# 03_-_SAMA7G54-MPU.net
KiCad netlist of a schematic drawn in Altium Designer
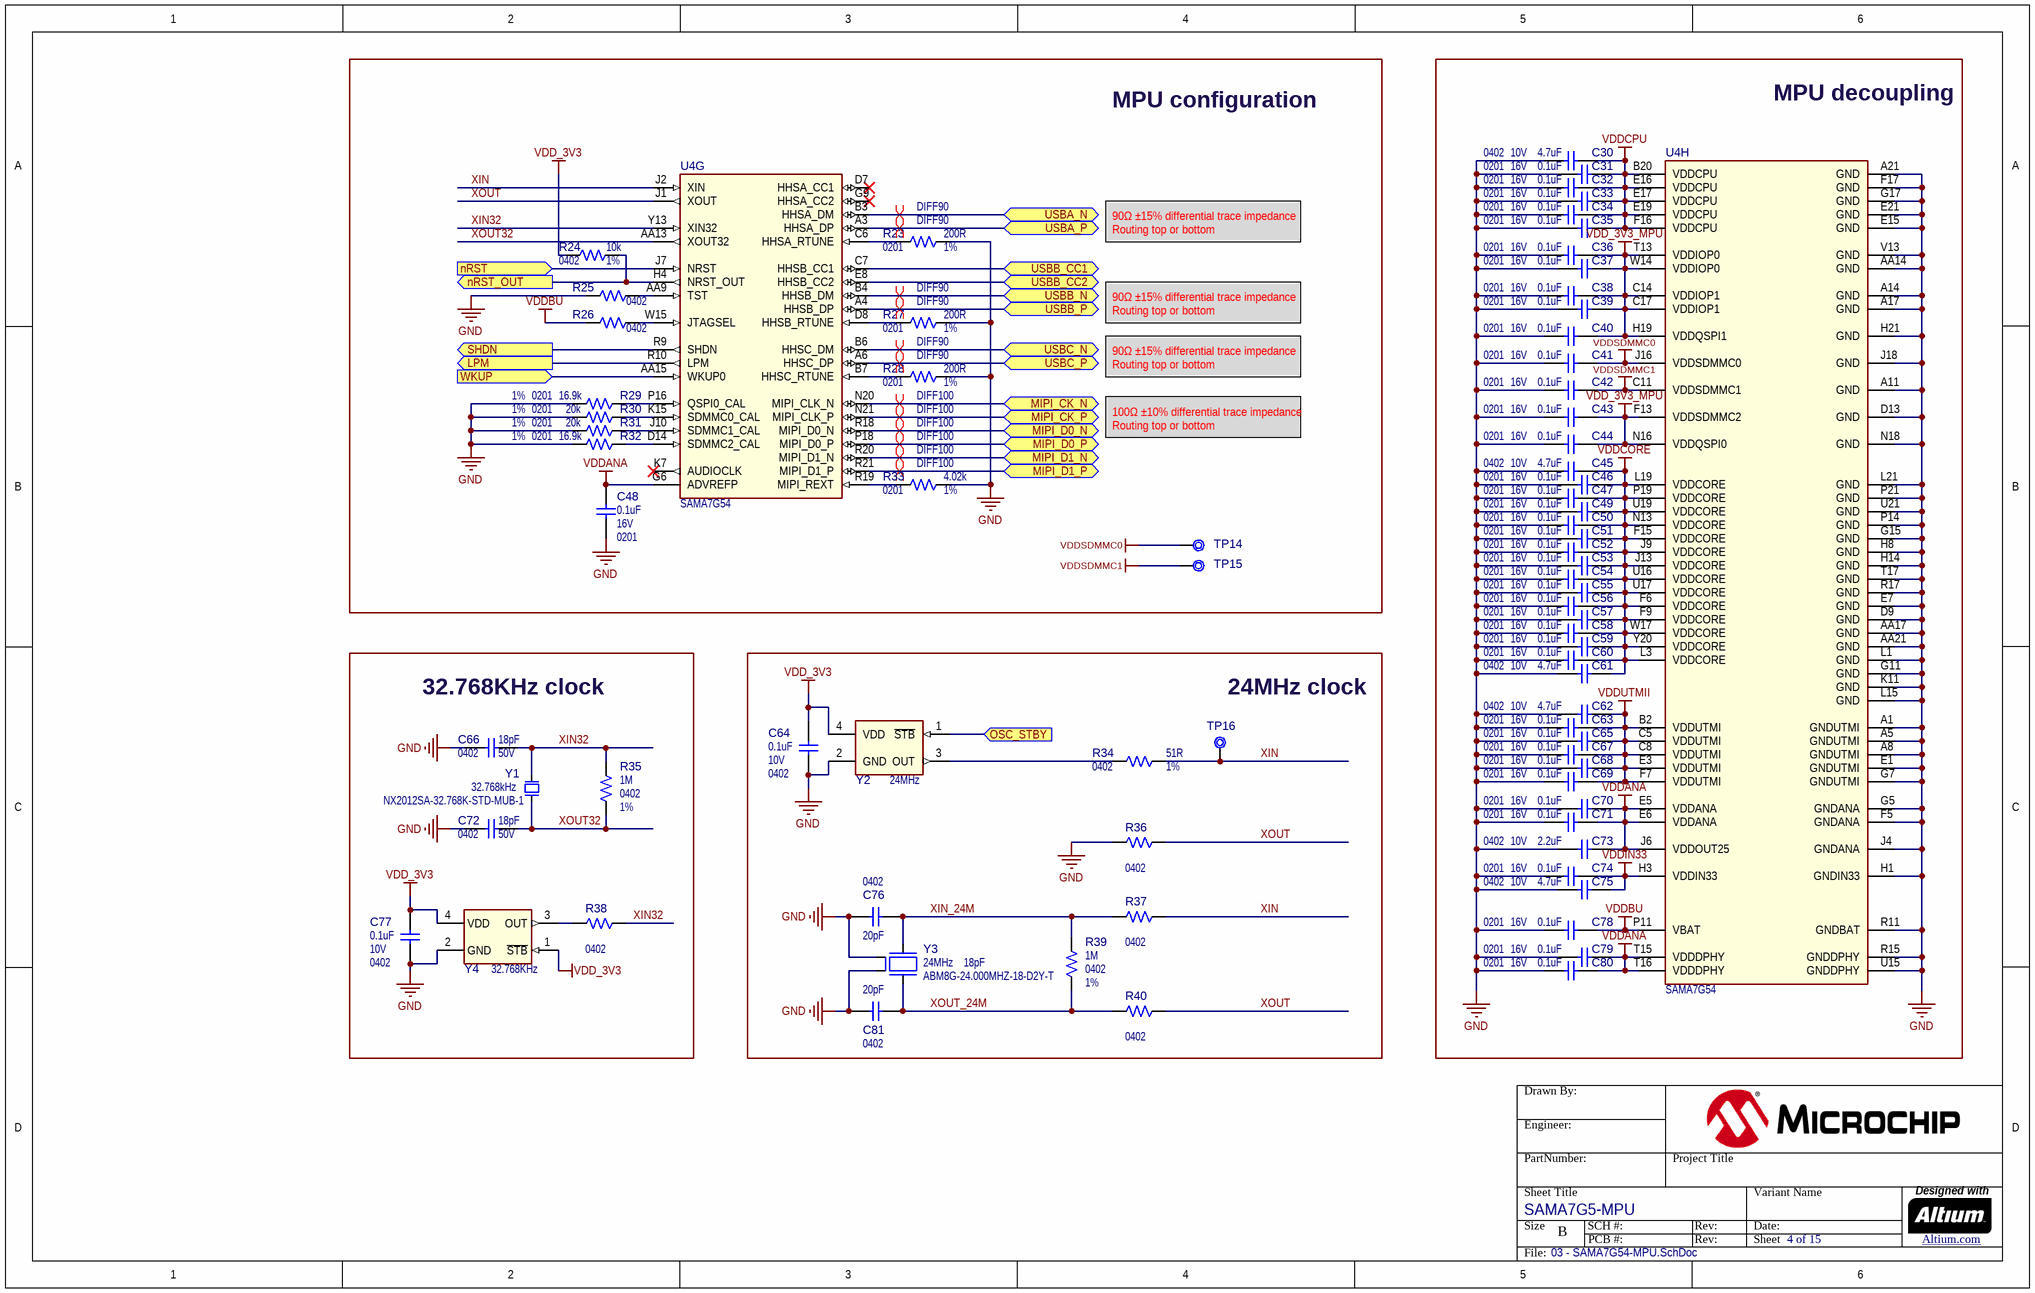
[diagram p0: 03 - SAMA7G54-MPU.SchDoc]

(export (version "E")
  (design (tool "Eeschema 10.0.6"))
  (components
    (comp (ref "C30")
      (value "4.7uF")
      (footprint "CAP_C_0402")
      (description "Capacitor")
      (fields
        (field (name "VOLTAGE") "10V")
        (field (name "PACKAGE") "0402")
        (field (name "TOLERANCE") "10%")
        (field (name "Comment") "Capacitor NP")
        (field (name "OWNER") "Jesus Aviles")
      )
      (libsource (lib "MCHP-CDB") (part "Capacitor NP"))
    )
    (comp (ref "C31")
      (value "0.1uF")
      (footprint "CAP_C_0201")
      (description "Capacitor")
      (fields
        (field (name "VOLTAGE") "16V")
        (field (name "PACKAGE") "0201")
        (field (name "TOLERANCE") "10%")
        (field (name "Comment") "Capacitor NP")
        (field (name "OWNER") "Dragos Danaila")
      )
      (libsource (lib "MCHP-CDB") (part "Capacitor NP"))
    )
    (comp (ref "C32")
      (value "0.1uF")
      (footprint "CAP_C_0201")
      (description "Capacitor")
      (fields
        (field (name "VOLTAGE") "16V")
        (field (name "PACKAGE") "0201")
        (field (name "TOLERANCE") "10%")
        (field (name "Comment") "Capacitor NP")
        (field (name "OWNER") "Dragos Danaila")
      )
      (libsource (lib "MCHP-CDB") (part "Capacitor NP"))
    )
    (comp (ref "C33")
      (value "0.1uF")
      (footprint "CAP_C_0201")
      (description "Capacitor")
      (fields
        (field (name "VOLTAGE") "16V")
        (field (name "PACKAGE") "0201")
        (field (name "TOLERANCE") "10%")
        (field (name "Comment") "Capacitor NP")
        (field (name "OWNER") "Dragos Danaila")
      )
      (libsource (lib "MCHP-CDB") (part "Capacitor NP"))
    )
    (comp (ref "C34")
      (value "0.1uF")
      (footprint "CAP_C_0201")
      (description "Capacitor")
      (fields
        (field (name "VOLTAGE") "16V")
        (field (name "PACKAGE") "0201")
        (field (name "TOLERANCE") "10%")
        (field (name "Comment") "Capacitor NP")
        (field (name "OWNER") "Dragos Danaila")
      )
      (libsource (lib "MCHP-CDB") (part "Capacitor NP"))
    )
    (comp (ref "C35")
      (value "0.1uF")
      (footprint "CAP_C_0201")
      (description "Capacitor")
      (fields
        (field (name "VOLTAGE") "16V")
        (field (name "PACKAGE") "0201")
        (field (name "TOLERANCE") "10%")
        (field (name "Comment") "Capacitor NP")
        (field (name "OWNER") "Dragos Danaila")
      )
      (libsource (lib "MCHP-CDB") (part "Capacitor NP"))
    )
    (comp (ref "C36")
      (value "0.1uF")
      (footprint "CAP_C_0201")
      (description "Capacitor")
      (fields
        (field (name "VOLTAGE") "16V")
        (field (name "PACKAGE") "0201")
        (field (name "TOLERANCE") "10%")
        (field (name "Comment") "Capacitor NP")
        (field (name "OWNER") "Dragos Danaila")
      )
      (libsource (lib "MCHP-CDB") (part "Capacitor NP"))
    )
    (comp (ref "C37")
      (value "0.1uF")
      (footprint "CAP_C_0201")
      (description "Capacitor")
      (fields
        (field (name "VOLTAGE") "16V")
        (field (name "PACKAGE") "0201")
        (field (name "TOLERANCE") "10%")
        (field (name "Comment") "Capacitor NP")
        (field (name "OWNER") "Dragos Danaila")
      )
      (libsource (lib "MCHP-CDB") (part "Capacitor NP"))
    )
    (comp (ref "C38")
      (value "0.1uF")
      (footprint "CAP_C_0201")
      (description "Capacitor")
      (fields
        (field (name "VOLTAGE") "16V")
        (field (name "PACKAGE") "0201")
        (field (name "TOLERANCE") "10%")
        (field (name "Comment") "Capacitor NP")
        (field (name "OWNER") "Dragos Danaila")
      )
      (libsource (lib "MCHP-CDB") (part "Capacitor NP"))
    )
    (comp (ref "C39")
      (value "0.1uF")
      (footprint "CAP_C_0201")
      (description "Capacitor")
      (fields
        (field (name "VOLTAGE") "16V")
        (field (name "PACKAGE") "0201")
        (field (name "TOLERANCE") "10%")
        (field (name "Comment") "Capacitor NP")
        (field (name "OWNER") "Dragos Danaila")
      )
      (libsource (lib "MCHP-CDB") (part "Capacitor NP"))
    )
    (comp (ref "C40")
      (value "0.1uF")
      (footprint "CAP_C_0201")
      (description "Capacitor")
      (fields
        (field (name "VOLTAGE") "16V")
        (field (name "PACKAGE") "0201")
        (field (name "TOLERANCE") "10%")
        (field (name "Comment") "Capacitor NP")
        (field (name "OWNER") "Dragos Danaila")
      )
      (libsource (lib "MCHP-CDB") (part "Capacitor NP"))
    )
    (comp (ref "C41")
      (value "0.1uF")
      (footprint "CAP_C_0201")
      (description "Capacitor")
      (fields
        (field (name "VOLTAGE") "16V")
        (field (name "PACKAGE") "0201")
        (field (name "TOLERANCE") "10%")
        (field (name "Comment") "Capacitor NP")
        (field (name "OWNER") "Dragos Danaila")
      )
      (libsource (lib "MCHP-CDB") (part "Capacitor NP"))
    )
    (comp (ref "C42")
      (value "0.1uF")
      (footprint "CAP_C_0201")
      (description "Capacitor")
      (fields
        (field (name "VOLTAGE") "16V")
        (field (name "PACKAGE") "0201")
        (field (name "TOLERANCE") "10%")
        (field (name "Comment") "Capacitor NP")
        (field (name "OWNER") "Dragos Danaila")
      )
      (libsource (lib "MCHP-CDB") (part "Capacitor NP"))
    )
    (comp (ref "C43")
      (value "0.1uF")
      (footprint "CAP_C_0201")
      (description "Capacitor")
      (fields
        (field (name "VOLTAGE") "16V")
        (field (name "PACKAGE") "0201")
        (field (name "TOLERANCE") "10%")
        (field (name "Comment") "Capacitor NP")
        (field (name "OWNER") "Dragos Danaila")
      )
      (libsource (lib "MCHP-CDB") (part "Capacitor NP"))
    )
    (comp (ref "C44")
      (value "0.1uF")
      (footprint "CAP_C_0201")
      (description "Capacitor")
      (fields
        (field (name "VOLTAGE") "16V")
        (field (name "PACKAGE") "0201")
        (field (name "TOLERANCE") "10%")
        (field (name "Comment") "Capacitor NP")
        (field (name "OWNER") "Dragos Danaila")
      )
      (libsource (lib "MCHP-CDB") (part "Capacitor NP"))
    )
    (comp (ref "C45")
      (value "4.7uF")
      (footprint "CAP_C_0402")
      (description "Capacitor")
      (fields
        (field (name "VOLTAGE") "10V")
        (field (name "PACKAGE") "0402")
        (field (name "TOLERANCE") "10%")
        (field (name "Comment") "Capacitor NP")
        (field (name "OWNER") "Jesus Aviles")
      )
      (libsource (lib "MCHP-CDB") (part "Capacitor NP"))
    )
    (comp (ref "C46")
      (value "0.1uF")
      (footprint "CAP_C_0201")
      (description "Capacitor")
      (fields
        (field (name "VOLTAGE") "16V")
        (field (name "PACKAGE") "0201")
        (field (name "TOLERANCE") "10%")
        (field (name "Comment") "Capacitor NP")
        (field (name "OWNER") "Dragos Danaila")
      )
      (libsource (lib "MCHP-CDB") (part "Capacitor NP"))
    )
    (comp (ref "C47")
      (value "0.1uF")
      (footprint "CAP_C_0201")
      (description "Capacitor")
      (fields
        (field (name "VOLTAGE") "16V")
        (field (name "PACKAGE") "0201")
        (field (name "TOLERANCE") "10%")
        (field (name "Comment") "Capacitor NP")
        (field (name "OWNER") "Dragos Danaila")
      )
      (libsource (lib "MCHP-CDB") (part "Capacitor NP"))
    )
    (comp (ref "C48")
      (value "0.1uF")
      (footprint "CAP_C_0201")
      (description "Capacitor")
      (fields
        (field (name "VOLTAGE") "16V")
        (field (name "PACKAGE") "0201")
        (field (name "TOLERANCE") "10%")
        (field (name "Comment") "Capacitor NP")
        (field (name "OWNER") "Dragos Danaila")
      )
      (libsource (lib "MCHP-CDB") (part "Capacitor NP"))
    )
    (comp (ref "C49")
      (value "0.1uF")
      (footprint "CAP_C_0201")
      (description "Capacitor")
      (fields
        (field (name "VOLTAGE") "16V")
        (field (name "PACKAGE") "0201")
        (field (name "TOLERANCE") "10%")
        (field (name "Comment") "Capacitor NP")
        (field (name "OWNER") "Dragos Danaila")
      )
      (libsource (lib "MCHP-CDB") (part "Capacitor NP"))
    )
    (comp (ref "C50")
      (value "0.1uF")
      (footprint "CAP_C_0201")
      (description "Capacitor")
      (fields
        (field (name "VOLTAGE") "16V")
        (field (name "PACKAGE") "0201")
        (field (name "TOLERANCE") "10%")
        (field (name "Comment") "Capacitor NP")
        (field (name "OWNER") "Dragos Danaila")
      )
      (libsource (lib "MCHP-CDB") (part "Capacitor NP"))
    )
    (comp (ref "C51")
      (value "0.1uF")
      (footprint "CAP_C_0201")
      (description "Capacitor")
      (fields
        (field (name "VOLTAGE") "16V")
        (field (name "PACKAGE") "0201")
        (field (name "TOLERANCE") "10%")
        (field (name "Comment") "Capacitor NP")
        (field (name "OWNER") "Dragos Danaila")
      )
      (libsource (lib "MCHP-CDB") (part "Capacitor NP"))
    )
    (comp (ref "C52")
      (value "0.1uF")
      (footprint "CAP_C_0201")
      (description "Capacitor")
      (fields
        (field (name "VOLTAGE") "16V")
        (field (name "PACKAGE") "0201")
        (field (name "TOLERANCE") "10%")
        (field (name "Comment") "Capacitor NP")
        (field (name "OWNER") "Dragos Danaila")
      )
      (libsource (lib "MCHP-CDB") (part "Capacitor NP"))
    )
    (comp (ref "C53")
      (value "0.1uF")
      (footprint "CAP_C_0201")
      (description "Capacitor")
      (fields
        (field (name "VOLTAGE") "16V")
        (field (name "PACKAGE") "0201")
        (field (name "TOLERANCE") "10%")
        (field (name "Comment") "Capacitor NP")
        (field (name "OWNER") "Dragos Danaila")
      )
      (libsource (lib "MCHP-CDB") (part "Capacitor NP"))
    )
    (comp (ref "C54")
      (value "0.1uF")
      (footprint "CAP_C_0201")
      (description "Capacitor")
      (fields
        (field (name "VOLTAGE") "16V")
        (field (name "PACKAGE") "0201")
        (field (name "TOLERANCE") "10%")
        (field (name "Comment") "Capacitor NP")
        (field (name "OWNER") "Dragos Danaila")
      )
      (libsource (lib "MCHP-CDB") (part "Capacitor NP"))
    )
    (comp (ref "C55")
      (value "0.1uF")
      (footprint "CAP_C_0201")
      (description "Capacitor")
      (fields
        (field (name "VOLTAGE") "16V")
        (field (name "PACKAGE") "0201")
        (field (name "TOLERANCE") "10%")
        (field (name "Comment") "Capacitor NP")
        (field (name "OWNER") "Dragos Danaila")
      )
      (libsource (lib "MCHP-CDB") (part "Capacitor NP"))
    )
    (comp (ref "C56")
      (value "0.1uF")
      (footprint "CAP_C_0201")
      (description "Capacitor")
      (fields
        (field (name "VOLTAGE") "16V")
        (field (name "PACKAGE") "0201")
        (field (name "TOLERANCE") "10%")
        (field (name "Comment") "Capacitor NP")
        (field (name "OWNER") "Dragos Danaila")
      )
      (libsource (lib "MCHP-CDB") (part "Capacitor NP"))
    )
    (comp (ref "C57")
      (value "0.1uF")
      (footprint "CAP_C_0201")
      (description "Capacitor")
      (fields
        (field (name "VOLTAGE") "16V")
        (field (name "PACKAGE") "0201")
        (field (name "TOLERANCE") "10%")
        (field (name "Comment") "Capacitor NP")
        (field (name "OWNER") "Dragos Danaila")
      )
      (libsource (lib "MCHP-CDB") (part "Capacitor NP"))
    )
    (comp (ref "C58")
      (value "0.1uF")
      (footprint "CAP_C_0201")
      (description "Capacitor")
      (fields
        (field (name "VOLTAGE") "16V")
        (field (name "PACKAGE") "0201")
        (field (name "TOLERANCE") "10%")
        (field (name "Comment") "Capacitor NP")
        (field (name "OWNER") "Dragos Danaila")
      )
      (libsource (lib "MCHP-CDB") (part "Capacitor NP"))
    )
    (comp (ref "C59")
      (value "0.1uF")
      (footprint "CAP_C_0201")
      (description "Capacitor")
      (fields
        (field (name "VOLTAGE") "16V")
        (field (name "PACKAGE") "0201")
        (field (name "TOLERANCE") "10%")
        (field (name "Comment") "Capacitor NP")
        (field (name "OWNER") "Dragos Danaila")
      )
      (libsource (lib "MCHP-CDB") (part "Capacitor NP"))
    )
    (comp (ref "C60")
      (value "0.1uF")
      (footprint "CAP_C_0201")
      (description "Capacitor")
      (fields
        (field (name "VOLTAGE") "16V")
        (field (name "PACKAGE") "0201")
        (field (name "TOLERANCE") "10%")
        (field (name "Comment") "Capacitor NP")
        (field (name "OWNER") "Dragos Danaila")
      )
      (libsource (lib "MCHP-CDB") (part "Capacitor NP"))
    )
    (comp (ref "C61")
      (value "4.7uF")
      (footprint "CAP_C_0402")
      (description "Capacitor")
      (fields
        (field (name "VOLTAGE") "10V")
        (field (name "PACKAGE") "0402")
        (field (name "TOLERANCE") "10%")
        (field (name "Comment") "Capacitor NP")
        (field (name "OWNER") "Jesus Aviles")
      )
      (libsource (lib "MCHP-CDB") (part "Capacitor NP"))
    )
    (comp (ref "C62")
      (value "4.7uF")
      (footprint "CAP_C_0402")
      (description "Capacitor")
      (fields
        (field (name "VOLTAGE") "10V")
        (field (name "PACKAGE") "0402")
        (field (name "TOLERANCE") "10%")
        (field (name "Comment") "Capacitor NP")
        (field (name "OWNER") "Jesus Aviles")
      )
      (libsource (lib "MCHP-CDB") (part "Capacitor NP"))
    )
    (comp (ref "C63")
      (value "0.1uF")
      (footprint "CAP_C_0201")
      (description "Capacitor")
      (fields
        (field (name "VOLTAGE") "16V")
        (field (name "PACKAGE") "0201")
        (field (name "TOLERANCE") "10%")
        (field (name "Comment") "Capacitor NP")
        (field (name "OWNER") "Dragos Danaila")
      )
      (libsource (lib "MCHP-CDB") (part "Capacitor NP"))
    )
    (comp (ref "C64")
      (value "0.1uF")
      (footprint "CAP_C_0402")
      (description "Capacitor")
      (fields
        (field (name "VOLTAGE") "10V")
        (field (name "PACKAGE") "0402")
        (field (name "TOLERANCE") "10%")
        (field (name "Comment") "Capacitor NP")
        (field (name "OWNER") "Tad Ahlvers")
      )
      (libsource (lib "MCHP-CDB") (part "Capacitor NP"))
    )
    (comp (ref "C65")
      (value "0.1uF")
      (footprint "CAP_C_0201")
      (description "Capacitor")
      (fields
        (field (name "VOLTAGE") "16V")
        (field (name "PACKAGE") "0201")
        (field (name "TOLERANCE") "10%")
        (field (name "Comment") "Capacitor NP")
        (field (name "OWNER") "Dragos Danaila")
      )
      (libsource (lib "MCHP-CDB") (part "Capacitor NP"))
    )
    (comp (ref "C66")
      (value "18pF")
      (footprint "CAP_C_0402")
      (fields
        (field (name "VOLTAGE") "50V")
        (field (name "PACKAGE") "0402")
        (field (name "TOLERANCE") "5%")
        (field (name "Comment") "Capacitor NP")
        (field (name "OWNER") "Tad Ahlvers")
      )
      (libsource (lib "") (part "Capacitor NP_1"))
    )
    (comp (ref "C67")
      (value "0.1uF")
      (footprint "CAP_C_0201")
      (description "Capacitor")
      (fields
        (field (name "VOLTAGE") "16V")
        (field (name "PACKAGE") "0201")
        (field (name "TOLERANCE") "10%")
        (field (name "Comment") "Capacitor NP")
        (field (name "OWNER") "Dragos Danaila")
      )
      (libsource (lib "MCHP-CDB") (part "Capacitor NP"))
    )
    (comp (ref "C68")
      (value "0.1uF")
      (footprint "CAP_C_0201")
      (description "Capacitor")
      (fields
        (field (name "VOLTAGE") "16V")
        (field (name "PACKAGE") "0201")
        (field (name "TOLERANCE") "10%")
        (field (name "Comment") "Capacitor NP")
        (field (name "OWNER") "Dragos Danaila")
      )
      (libsource (lib "MCHP-CDB") (part "Capacitor NP"))
    )
    (comp (ref "C69")
      (value "0.1uF")
      (footprint "CAP_C_0201")
      (description "Capacitor")
      (fields
        (field (name "VOLTAGE") "16V")
        (field (name "PACKAGE") "0201")
        (field (name "TOLERANCE") "10%")
        (field (name "Comment") "Capacitor NP")
        (field (name "OWNER") "Dragos Danaila")
      )
      (libsource (lib "MCHP-CDB") (part "Capacitor NP"))
    )
    (comp (ref "C70")
      (value "0.1uF")
      (footprint "CAP_C_0201")
      (description "Capacitor")
      (fields
        (field (name "VOLTAGE") "16V")
        (field (name "PACKAGE") "0201")
        (field (name "TOLERANCE") "10%")
        (field (name "Comment") "Capacitor NP")
        (field (name "OWNER") "Dragos Danaila")
      )
      (libsource (lib "MCHP-CDB") (part "Capacitor NP"))
    )
    (comp (ref "C71")
      (value "0.1uF")
      (footprint "CAP_C_0201")
      (description "Capacitor")
      (fields
        (field (name "VOLTAGE") "16V")
        (field (name "PACKAGE") "0201")
        (field (name "TOLERANCE") "10%")
        (field (name "Comment") "Capacitor NP")
        (field (name "OWNER") "Dragos Danaila")
      )
      (libsource (lib "MCHP-CDB") (part "Capacitor NP"))
    )
    (comp (ref "C72")
      (value "18pF")
      (footprint "CAP_C_0402")
      (fields
        (field (name "VOLTAGE") "50V")
        (field (name "PACKAGE") "0402")
        (field (name "TOLERANCE") "5%")
        (field (name "Comment") "Capacitor NP")
        (field (name "OWNER") "Tad Ahlvers")
      )
      (libsource (lib "") (part "Capacitor NP_1"))
    )
    (comp (ref "C73")
      (value "2.2uF")
      (footprint "CAP_C_0402")
      (description "Capacitor")
      (fields
        (field (name "VOLTAGE") "10V")
        (field (name "PACKAGE") "0402")
        (field (name "TOLERANCE") "10%")
        (field (name "Comment") "Capacitor NP")
        (field (name "OWNER") "Sorin Stanoaia")
      )
      (libsource (lib "MCHP-CDB") (part "Capacitor NP"))
    )
    (comp (ref "C74")
      (value "0.1uF")
      (footprint "CAP_C_0201")
      (description "Capacitor")
      (fields
        (field (name "VOLTAGE") "16V")
        (field (name "PACKAGE") "0201")
        (field (name "TOLERANCE") "10%")
        (field (name "Comment") "Capacitor NP")
        (field (name "OWNER") "Dragos Danaila")
      )
      (libsource (lib "MCHP-CDB") (part "Capacitor NP"))
    )
    (comp (ref "C75")
      (value "4.7uF")
      (footprint "CAP_C_0402")
      (description "Capacitor")
      (fields
        (field (name "VOLTAGE") "10V")
        (field (name "PACKAGE") "0402")
        (field (name "TOLERANCE") "10%")
        (field (name "Comment") "Capacitor NP")
        (field (name "OWNER") "Jesus Aviles")
      )
      (libsource (lib "MCHP-CDB") (part "Capacitor NP"))
    )
    (comp (ref "C76")
      (value "20pF")
      (footprint "CAP_C_0402")
      (fields
        (field (name "VOLTAGE") "50V")
        (field (name "PACKAGE") "0402")
        (field (name "TOLERANCE") "2%")
        (field (name "Comment") "Capacitor NP")
        (field (name "OWNER") "Dragos Danaila")
      )
      (libsource (lib "") (part "Capacitor NP_1"))
    )
    (comp (ref "C77")
      (value "0.1uF")
      (footprint "CAP_C_0402")
      (description "Capacitor")
      (fields
        (field (name "VOLTAGE") "10V")
        (field (name "PACKAGE") "0402")
        (field (name "TOLERANCE") "10%")
        (field (name "Comment") "Capacitor NP")
        (field (name "OWNER") "Tad Ahlvers")
      )
      (libsource (lib "MCHP-CDB") (part "Capacitor NP"))
    )
    (comp (ref "C78")
      (value "0.1uF")
      (footprint "CAP_C_0201")
      (description "Capacitor")
      (fields
        (field (name "VOLTAGE") "16V")
        (field (name "PACKAGE") "0201")
        (field (name "TOLERANCE") "10%")
        (field (name "Comment") "Capacitor NP")
        (field (name "OWNER") "Dragos Danaila")
      )
      (libsource (lib "MCHP-CDB") (part "Capacitor NP"))
    )
    (comp (ref "C79")
      (value "0.1uF")
      (footprint "CAP_C_0201")
      (description "Capacitor")
      (fields
        (field (name "VOLTAGE") "16V")
        (field (name "PACKAGE") "0201")
        (field (name "TOLERANCE") "10%")
        (field (name "Comment") "Capacitor NP")
        (field (name "OWNER") "Dragos Danaila")
      )
      (libsource (lib "MCHP-CDB") (part "Capacitor NP"))
    )
    (comp (ref "C80")
      (value "0.1uF")
      (footprint "CAP_C_0201")
      (description "Capacitor")
      (fields
        (field (name "VOLTAGE") "16V")
        (field (name "PACKAGE") "0201")
        (field (name "TOLERANCE") "10%")
        (field (name "Comment") "Capacitor NP")
        (field (name "OWNER") "Dragos Danaila")
      )
      (libsource (lib "MCHP-CDB") (part "Capacitor NP"))
    )
    (comp (ref "C81")
      (value "20pF")
      (footprint "CAP_C_0402")
      (fields
        (field (name "VOLTAGE") "50V")
        (field (name "PACKAGE") "0402")
        (field (name "TOLERANCE") "2%")
        (field (name "Comment") "Capacitor NP")
        (field (name "OWNER") "Dragos Danaila")
      )
      (libsource (lib "") (part "Capacitor NP_1"))
    )
    (comp (ref "R23")
      (value "200R")
      (footprint "RES_C_0201")
      (description "Resistor")
      (fields
        (field (name "PACKAGE") "0201")
        (field (name "TOLERANCE") "1%")
        (field (name "POWER") "1/20W")
        (field (name "VOLTAGE") "30V")
        (field (name "OWNER") "Dragos Danaila")
      )
      (libsource (lib "MCHP-CDB") (part "Resistor"))
    )
    (comp (ref "R24")
      (value "10k")
      (footprint "RES_C_0402")
      (description "Resistor")
      (fields
        (field (name "PACKAGE") "0402")
        (field (name "TOLERANCE") "1%")
        (field (name "VOLTAGE") "50V")
        (field (name "POWER") "1/10W")
        (field (name "OWNER") "Brent Lanphear")
      )
      (libsource (lib "MCHP-CDB") (part "Resistor"))
    )
    (comp (ref "R25")
      (value "Resistor")
      (footprint "RES_C_0402")
      (fields
        (field (name "PACKAGE") "0402")
        (field (name "POWER") "1/16W")
        (field (name "VOLTAGE") "50V")
        (field (name "OWNER") "Dragos Danaila")
      )
      (libsource (lib "MCHP-CDB") (part "Resistor"))
    )
    (comp (ref "R26")
      (value "Resistor")
      (footprint "RES_C_0402")
      (fields
        (field (name "PACKAGE") "0402")
        (field (name "POWER") "1/16W")
        (field (name "VOLTAGE") "50V")
        (field (name "OWNER") "Dragos Danaila")
      )
      (libsource (lib "MCHP-CDB") (part "Resistor"))
    )
    (comp (ref "R27")
      (value "200R")
      (footprint "RES_C_0201")
      (description "Resistor")
      (fields
        (field (name "PACKAGE") "0201")
        (field (name "TOLERANCE") "1%")
        (field (name "POWER") "1/20W")
        (field (name "VOLTAGE") "30V")
        (field (name "OWNER") "Dragos Danaila")
      )
      (libsource (lib "MCHP-CDB") (part "Resistor"))
    )
    (comp (ref "R28")
      (value "200R")
      (footprint "RES_C_0201")
      (description "Resistor")
      (fields
        (field (name "PACKAGE") "0201")
        (field (name "TOLERANCE") "1%")
        (field (name "POWER") "1/20W")
        (field (name "VOLTAGE") "30V")
        (field (name "OWNER") "Dragos Danaila")
      )
      (libsource (lib "MCHP-CDB") (part "Resistor"))
    )
    (comp (ref "R29")
      (value "16.9k")
      (footprint "RES_C_0201")
      (description "Resistor")
      (fields
        (field (name "PACKAGE") "0201")
        (field (name "TOLERANCE") "1%")
        (field (name "POWER") "1/20W")
        (field (name "VOLTAGE") "25V")
        (field (name "OWNER") "Dragos Danaila")
      )
      (libsource (lib "MCHP-CDB") (part "Resistor"))
    )
    (comp (ref "R30")
      (value "20k")
      (footprint "RES_C_0201")
      (description "Resistor")
      (fields
        (field (name "PACKAGE") "0201")
        (field (name "TOLERANCE") "1%")
        (field (name "POWER") "1/20W")
        (field (name "VOLTAGE") "30V")
        (field (name "OWNER") "Ciprian Abramov")
      )
      (libsource (lib "MCHP-CDB") (part "Resistor"))
    )
    (comp (ref "R31")
      (value "20k")
      (footprint "RES_C_0201")
      (description "Resistor")
      (fields
        (field (name "PACKAGE") "0201")
        (field (name "TOLERANCE") "1%")
        (field (name "POWER") "1/20W")
        (field (name "VOLTAGE") "30V")
        (field (name "OWNER") "Ciprian Abramov")
      )
      (libsource (lib "MCHP-CDB") (part "Resistor"))
    )
    (comp (ref "R32")
      (value "16.9k")
      (footprint "RES_C_0201")
      (description "Resistor")
      (fields
        (field (name "PACKAGE") "0201")
        (field (name "TOLERANCE") "1%")
        (field (name "POWER") "1/20W")
        (field (name "VOLTAGE") "25V")
        (field (name "OWNER") "Dragos Danaila")
      )
      (libsource (lib "MCHP-CDB") (part "Resistor"))
    )
    (comp (ref "R33")
      (value "4.02k")
      (footprint "RES_C_0201")
      (description "Resistor")
      (fields
        (field (name "PACKAGE") "0201")
        (field (name "TOLERANCE") "1%")
        (field (name "POWER") "1/20W")
        (field (name "OWNER") "Ilie Galan")
      )
      (libsource (lib "MCHP-CDB") (part "Resistor"))
    )
    (comp (ref "R34")
      (value "51R")
      (footprint "RES_C_0402")
      (description "Resistor")
      (fields
        (field (name "PACKAGE") "0402")
        (field (name "TOLERANCE") "1%")
        (field (name "VOLTAGE") "50V")
        (field (name "POWER") "1/5W")
        (field (name "OWNER") "Dragos Danaila")
      )
      (libsource (lib "MCHP-CDB") (part "Resistor"))
    )
    (comp (ref "R35")
      (value "1M")
      (footprint "RES_C_0402")
      (description "Resistor")
      (fields
        (field (name "PACKAGE") "0402")
        (field (name "TOLERANCE") "1%")
        (field (name "VOLTAGE") "50V")
        (field (name "POWER") "1/10W")
        (field (name "OWNER") "Brent Lanphear")
      )
      (libsource (lib "MCHP-CDB") (part "Resistor"))
    )
    (comp (ref "R36")
      (value "Resistor")
      (footprint "RES_C_0402")
      (fields
        (field (name "PACKAGE") "0402")
        (field (name "POWER") "1/16W")
        (field (name "VOLTAGE") "50V")
        (field (name "OWNER") "Dragos Danaila")
      )
      (libsource (lib "MCHP-CDB") (part "Resistor"))
    )
    (comp (ref "R37")
      (value "Resistor")
      (footprint "RES_C_0402")
      (fields
        (field (name "PACKAGE") "0402")
        (field (name "POWER") "1/16W")
        (field (name "VOLTAGE") "50V")
        (field (name "OWNER") "Dragos Danaila")
      )
      (libsource (lib "MCHP-CDB") (part "Resistor"))
    )
    (comp (ref "R38")
      (value "Resistor")
      (footprint "RES_C_0402")
      (fields
        (field (name "PACKAGE") "0402")
        (field (name "POWER") "1/16W")
        (field (name "VOLTAGE") "50V")
        (field (name "OWNER") "Dragos Danaila")
      )
      (libsource (lib "MCHP-CDB") (part "Resistor"))
    )
    (comp (ref "R39")
      (value "1M")
      (footprint "RES_C_0402")
      (description "Resistor")
      (fields
        (field (name "PACKAGE") "0402")
        (field (name "TOLERANCE") "1%")
        (field (name "VOLTAGE") "50V")
        (field (name "POWER") "1/10W")
        (field (name "OWNER") "Brent Lanphear")
      )
      (libsource (lib "MCHP-CDB") (part "Resistor"))
    )
    (comp (ref "R40")
      (value "Resistor")
      (footprint "RES_C_0402")
      (fields
        (field (name "PACKAGE") "0402")
        (field (name "POWER") "1/16W")
        (field (name "VOLTAGE") "50V")
        (field (name "OWNER") "Dragos Danaila")
      )
      (libsource (lib "MCHP-CDB") (part "Resistor"))
    )
    (comp (ref "TP14")
      (value "Test Point No BOM")
      (footprint "TP_1mm_SMD")
      (description "Test Point")
      (fields (field (name "OWNER") "Cristian Papuc"))
      (libsource (lib "MCHP-CDB") (part "Test Point No BOM"))
    )
    (comp (ref "TP15")
      (value "Test Point No BOM")
      (footprint "TP_1mm_SMD")
      (description "Test Point")
      (fields (field (name "OWNER") "Cristian Papuc"))
      (libsource (lib "MCHP-CDB") (part "Test Point No BOM"))
    )
    (comp (ref "TP16")
      (value "Test Point No BOM")
      (footprint "TP_1mm_SMD")
      (description "Test Point")
      (fields (field (name "OWNER") "Cristian Papuc"))
      (libsource (lib "MCHP-CDB") (part "Test Point No BOM"))
    )
    (comp (ref "U4")
      (value "SAMA7G54")
      (footprint "TFBGA-343_14x14")
      (description "SAMA7G54 MPU 1000MHz Cortex-A7 TFBGA-343")
      (fields (field (name "OWNER") "Ciprian Abramov"))
      (libsource (lib "MCHP-CDB") (part "SAMA7G54 TFBGA-343"))
    )
    (comp (ref "Y1")
      (value "32.768kHz")
      (footprint "CRYSTAL_NX2012SA")
      (description "Crystal")
      (fields
        (field (name "TOLERANCE") "±20ppm")
        (field (name "MANUFACTURER PART NUMBER 1") "NX2012SA-32.768K-STD-MUB-1")
        (field (name "Comment") "Crystal 2 Pins")
        (field (name "OWNER") "Jamus Griego")
      )
      (libsource (lib "MCHP-CDB") (part "Crystal 2 Pins"))
    )
    (comp (ref "Y2")
      (value "24MHz")
      (footprint "DFN-4_2.5x2")
      (fields (field (name "Comment") "DSC10xx DFN-4") (field (name "OWNER") "Maurizio Gavardoni"))
      (libsource (lib "MCHP-CDB") (part "DSC10xx DFN-4"))
    )
    (comp (ref "Y3")
      (value "24MHz")
      (footprint "CRYSTAL_ABM8G")
      (description "Crystal")
      (fields
        (field (name "LOAD CAPACITANCE") "18pF")
        (field (name "MANUFACTURER PART NUMBER 1") "ABM8G-24.000MHZ-18-D2Y-T")
        (field (name "Comment") "Crystal 4 Pins")
        (field (name "OWNER") "Mark Loper")
      )
      (libsource (lib "MCHP-CDB") (part "Crystal 4 Pins"))
    )
    (comp (ref "Y4")
      (value "32.768KHz")
      (footprint "DFN-4_2x1.6")
      (fields (field (name "Comment") "DSC60xx DFN-4_LGA-4") (field (name "OWNER") "Ciprian Abramov"))
      (libsource (lib "MCHP-CDB") (part "DSC60xx DFN-4_LGA-4"))
    )
  )
  (nets
    (net (code "1") (name "/LPM") (class "Default")
      (node (ref "U4") (pin "R10") (pinfunction "LPM_R10") (pintype "output"))
    )
    (net (code "2") (name "/MIPI_CK_N") (class "Default")
      (node (ref "U4") (pin "N20") (pinfunction "MIPI_CLK_N_N20") (pintype "bidirectional"))
    )
    (net (code "3") (name "/MIPI_CK_P") (class "Default")
      (node (ref "U4") (pin "N21") (pinfunction "MIPI_CLK_P_N21") (pintype "bidirectional"))
    )
    (net (code "4") (name "/MIPI_D0_N") (class "Default")
      (node (ref "U4") (pin "R18") (pinfunction "MIPI_D0_N_R18") (pintype "bidirectional"))
    )
    (net (code "5") (name "/MIPI_D0_P") (class "Default")
      (node (ref "U4") (pin "P18") (pinfunction "MIPI_D0_P_P18") (pintype "bidirectional"))
    )
    (net (code "6") (name "/MIPI_D1_N") (class "Default")
      (node (ref "U4") (pin "R20") (pinfunction "MIPI_D1_N_R20") (pintype "bidirectional"))
    )
    (net (code "7") (name "/MIPI_D1_P") (class "Default")
      (node (ref "U4") (pin "R21") (pinfunction "MIPI_D1_P_R21") (pintype "bidirectional"))
    )
    (net (code "8") (name "/OSC_STBY") (class "Default")
      (node (ref "Y2") (pin "1") (pinfunction "~{STB}_1") (pintype "input"))
    )
    (net (code "9") (name "/SHDN") (class "Default")
      (node (ref "U4") (pin "R9") (pinfunction "SHDN_R9") (pintype "output"))
    )
    (net (code "10") (name "/USBA_N") (class "Default")
      (node (ref "U4") (pin "B3") (pinfunction "HHSA_DM_B3") (pintype "bidirectional"))
    )
    (net (code "11") (name "/USBA_P") (class "Default")
      (node (ref "U4") (pin "A3") (pinfunction "HHSA_DP_A3") (pintype "bidirectional"))
    )
    (net (code "12") (name "/USBB_CC1") (class "Default")
      (node (ref "U4") (pin "C7") (pinfunction "HHSB_CC1_C7") (pintype "bidirectional"))
    )
    (net (code "13") (name "/USBB_CC2") (class "Default")
      (node (ref "U4") (pin "E8") (pinfunction "HHSB_CC2_E8") (pintype "bidirectional"))
    )
    (net (code "14") (name "/USBB_N") (class "Default")
      (node (ref "U4") (pin "B4") (pinfunction "HHSB_DM_B4") (pintype "bidirectional"))
    )
    (net (code "15") (name "/USBB_P") (class "Default")
      (node (ref "U4") (pin "A4") (pinfunction "HHSB_DP_A4") (pintype "bidirectional"))
    )
    (net (code "16") (name "/USBC_N") (class "Default")
      (node (ref "U4") (pin "B6") (pinfunction "HHSC_DM_B6") (pintype "bidirectional"))
    )
    (net (code "17") (name "/USBC_P") (class "Default")
      (node (ref "U4") (pin "A6") (pinfunction "HHSC_DP_A6") (pintype "bidirectional"))
    )
    (net (code "18") (name "/WKUP") (class "Default")
      (node (ref "U4") (pin "AA15") (pinfunction "WKUP0_AA15") (pintype "input"))
    )
    (net (code "19") (name "/XIN") (class "Default")
      (node (ref "R34") (pin "2") (pinfunction "2_2") (pintype "passive"))
      (node (ref "R37") (pin "2") (pinfunction "2_2") (pintype "passive"))
      (node (ref "TP16") (pin "1") (pinfunction "1_1") (pintype "passive"))
      (node (ref "U4") (pin "J2") (pinfunction "XIN_J2") (pintype "input"))
    )
    (net (code "20") (name "/XIN32") (class "Default")
      (node (ref "C66") (pin "2") (pinfunction "2_2") (pintype "passive"))
      (node (ref "R35") (pin "2") (pinfunction "2_2") (pintype "passive"))
      (node (ref "R38") (pin "2") (pinfunction "2_2") (pintype "passive"))
      (node (ref "U4") (pin "Y13") (pinfunction "XIN32_Y13") (pintype "input"))
      (node (ref "Y1") (pin "2") (pinfunction "Osc2_2") (pintype "passive"))
    )
    (net (code "21") (name "/XIN_24M") (class "Default")
      (node (ref "C76") (pin "2") (pinfunction "2_2") (pintype "passive"))
      (node (ref "R37") (pin "1") (pinfunction "1_1") (pintype "passive"))
      (node (ref "R39") (pin "2") (pinfunction "2_2") (pintype "passive"))
      (node (ref "Y3") (pin "3") (pinfunction "Osc2_3") (pintype "passive"))
    )
    (net (code "22") (name "/XOUT") (class "Default")
      (node (ref "R36") (pin "2") (pinfunction "2_2") (pintype "passive"))
      (node (ref "R40") (pin "2") (pinfunction "2_2") (pintype "passive"))
      (node (ref "U4") (pin "J1") (pinfunction "XOUT_J1") (pintype "output"))
    )
    (net (code "23") (name "/XOUT32") (class "Default")
      (node (ref "C72") (pin "2") (pinfunction "2_2") (pintype "passive"))
      (node (ref "R35") (pin "1") (pinfunction "1_1") (pintype "passive"))
      (node (ref "U4") (pin "AA13") (pinfunction "XOUT32_AA13") (pintype "output"))
      (node (ref "Y1") (pin "1") (pinfunction "Osc1_1") (pintype "passive"))
    )
    (net (code "24") (name "/XOUT_24M") (class "Default")
      (node (ref "C81") (pin "2") (pinfunction "2_2") (pintype "passive"))
      (node (ref "R39") (pin "1") (pinfunction "1_1") (pintype "passive"))
      (node (ref "R40") (pin "1") (pinfunction "1_1") (pintype "passive"))
      (node (ref "Y3") (pin "1") (pinfunction "Osc1_1") (pintype "passive"))
    )
    (net (code "25") (name "/nRST") (class "Default")
      (node (ref "U4") (pin "J7") (pinfunction "NRST_J7") (pintype "input"))
    )
    (net (code "26") (name "/nRST_OUT") (class "Default")
      (node (ref "R24") (pin "1") (pinfunction "1_1") (pintype "passive"))
      (node (ref "U4") (pin "H4") (pinfunction "NRST_OUT_H4") (pintype "output"))
    )
    (net (code "27") (name "GND") (class "Default")
      (node (ref "C30") (pin "2") (pinfunction "2_2") (pintype "passive"))
      (node (ref "C31") (pin "2") (pinfunction "2_2") (pintype "passive"))
      (node (ref "C32") (pin "2") (pinfunction "2_2") (pintype "passive"))
      (node (ref "C33") (pin "2") (pinfunction "2_2") (pintype "passive"))
      (node (ref "C34") (pin "2") (pinfunction "2_2") (pintype "passive"))
      (node (ref "C35") (pin "2") (pinfunction "2_2") (pintype "passive"))
      (node (ref "C36") (pin "2") (pinfunction "2_2") (pintype "passive"))
      (node (ref "C37") (pin "2") (pinfunction "2_2") (pintype "passive"))
      (node (ref "C38") (pin "2") (pinfunction "2_2") (pintype "passive"))
      (node (ref "C39") (pin "2") (pinfunction "2_2") (pintype "passive"))
      (node (ref "C40") (pin "2") (pinfunction "2_2") (pintype "passive"))
      (node (ref "C41") (pin "2") (pinfunction "2_2") (pintype "passive"))
      (node (ref "C42") (pin "2") (pinfunction "2_2") (pintype "passive"))
      (node (ref "C43") (pin "2") (pinfunction "2_2") (pintype "passive"))
      (node (ref "C44") (pin "2") (pinfunction "2_2") (pintype "passive"))
      (node (ref "C45") (pin "2") (pinfunction "2_2") (pintype "passive"))
      (node (ref "C46") (pin "2") (pinfunction "2_2") (pintype "passive"))
      (node (ref "C47") (pin "2") (pinfunction "2_2") (pintype "passive"))
      (node (ref "C48") (pin "1") (pinfunction "1_1") (pintype "passive"))
      (node (ref "C49") (pin "2") (pinfunction "2_2") (pintype "passive"))
      (node (ref "C50") (pin "2") (pinfunction "2_2") (pintype "passive"))
      (node (ref "C51") (pin "2") (pinfunction "2_2") (pintype "passive"))
      (node (ref "C52") (pin "2") (pinfunction "2_2") (pintype "passive"))
      (node (ref "C53") (pin "2") (pinfunction "2_2") (pintype "passive"))
      (node (ref "C54") (pin "2") (pinfunction "2_2") (pintype "passive"))
      (node (ref "C55") (pin "2") (pinfunction "2_2") (pintype "passive"))
      (node (ref "C56") (pin "2") (pinfunction "2_2") (pintype "passive"))
      (node (ref "C57") (pin "2") (pinfunction "2_2") (pintype "passive"))
      (node (ref "C58") (pin "2") (pinfunction "2_2") (pintype "passive"))
      (node (ref "C59") (pin "2") (pinfunction "2_2") (pintype "passive"))
      (node (ref "C60") (pin "2") (pinfunction "2_2") (pintype "passive"))
      (node (ref "C61") (pin "2") (pinfunction "2_2") (pintype "passive"))
      (node (ref "C62") (pin "2") (pinfunction "2_2") (pintype "passive"))
      (node (ref "C63") (pin "2") (pinfunction "2_2") (pintype "passive"))
      (node (ref "C64") (pin "1") (pinfunction "1_1") (pintype "passive"))
      (node (ref "C65") (pin "2") (pinfunction "2_2") (pintype "passive"))
      (node (ref "C66") (pin "1") (pinfunction "1_1") (pintype "passive"))
      (node (ref "C67") (pin "2") (pinfunction "2_2") (pintype "passive"))
      (node (ref "C68") (pin "2") (pinfunction "2_2") (pintype "passive"))
      (node (ref "C69") (pin "2") (pinfunction "2_2") (pintype "passive"))
      (node (ref "C70") (pin "2") (pinfunction "2_2") (pintype "passive"))
      (node (ref "C71") (pin "2") (pinfunction "2_2") (pintype "passive"))
      (node (ref "C72") (pin "1") (pinfunction "1_1") (pintype "passive"))
      (node (ref "C73") (pin "2") (pinfunction "2_2") (pintype "passive"))
      (node (ref "C74") (pin "2") (pinfunction "2_2") (pintype "passive"))
      (node (ref "C75") (pin "2") (pinfunction "2_2") (pintype "passive"))
      (node (ref "C76") (pin "1") (pinfunction "1_1") (pintype "passive"))
      (node (ref "C77") (pin "1") (pinfunction "1_1") (pintype "passive"))
      (node (ref "C78") (pin "2") (pinfunction "2_2") (pintype "passive"))
      (node (ref "C79") (pin "2") (pinfunction "2_2") (pintype "passive"))
      (node (ref "C80") (pin "2") (pinfunction "2_2") (pintype "passive"))
      (node (ref "C81") (pin "1") (pinfunction "1_1") (pintype "passive"))
      (node (ref "R23") (pin "2") (pinfunction "2_2") (pintype "passive"))
      (node (ref "R25") (pin "1") (pinfunction "1_1") (pintype "passive"))
      (node (ref "R27") (pin "2") (pinfunction "2_2") (pintype "passive"))
      (node (ref "R28") (pin "2") (pinfunction "2_2") (pintype "passive"))
      (node (ref "R29") (pin "1") (pinfunction "1_1") (pintype "passive"))
      (node (ref "R30") (pin "1") (pinfunction "1_1") (pintype "passive"))
      (node (ref "R31") (pin "1") (pinfunction "1_1") (pintype "passive"))
      (node (ref "R32") (pin "1") (pinfunction "1_1") (pintype "passive"))
      (node (ref "R33") (pin "2") (pinfunction "2_2") (pintype "passive"))
      (node (ref "R36") (pin "1") (pinfunction "1_1") (pintype "passive"))
      (node (ref "U4") (pin "A1") (pinfunction "GNDUTMI_A1") (pintype "power_in"))
      (node (ref "U4") (pin "A11") (pinfunction "GND_A11") (pintype "power_in"))
      (node (ref "U4") (pin "A14") (pinfunction "GND_A14") (pintype "power_in"))
      (node (ref "U4") (pin "A17") (pinfunction "GND_A17") (pintype "power_in"))
      (node (ref "U4") (pin "A21") (pinfunction "GND_A21") (pintype "power_in"))
      (node (ref "U4") (pin "A5") (pinfunction "GNDUTMI_A5") (pintype "power_in"))
      (node (ref "U4") (pin "A8") (pinfunction "GNDUTMI_A8") (pintype "power_in"))
      (node (ref "U4") (pin "AA14") (pinfunction "GND_AA14") (pintype "power_in"))
      (node (ref "U4") (pin "AA17") (pinfunction "GND_AA17") (pintype "power_in"))
      (node (ref "U4") (pin "AA21") (pinfunction "GND_AA21") (pintype "power_in"))
      (node (ref "U4") (pin "D13") (pinfunction "GND_D13") (pintype "power_in"))
      (node (ref "U4") (pin "D9") (pinfunction "GND_D9") (pintype "power_in"))
      (node (ref "U4") (pin "E1") (pinfunction "GNDUTMI_E1") (pintype "power_in"))
      (node (ref "U4") (pin "E15") (pinfunction "GND_E15") (pintype "power_in"))
      (node (ref "U4") (pin "E21") (pinfunction "GND_E21") (pintype "power_in"))
      (node (ref "U4") (pin "E7") (pinfunction "GND_E7") (pintype "power_in"))
      (node (ref "U4") (pin "F17") (pinfunction "GND_F17") (pintype "power_in"))
      (node (ref "U4") (pin "F5") (pinfunction "GNDANA_F5") (pintype "power_in"))
      (node (ref "U4") (pin "G11") (pinfunction "GND_G11") (pintype "power_in"))
      (node (ref "U4") (pin "G15") (pinfunction "GND_G15") (pintype "power_in"))
      (node (ref "U4") (pin "G17") (pinfunction "GND_G17") (pintype "power_in"))
      (node (ref "U4") (pin "G5") (pinfunction "GNDANA_G5") (pintype "power_in"))
      (node (ref "U4") (pin "G7") (pinfunction "GNDUTMI_G7") (pintype "power_in"))
      (node (ref "U4") (pin "H1") (pinfunction "GNDIN33_H1") (pintype "power_in"))
      (node (ref "U4") (pin "H14") (pinfunction "GND_H14") (pintype "power_in"))
      (node (ref "U4") (pin "H21") (pinfunction "GND_H21") (pintype "power_in"))
      (node (ref "U4") (pin "H8") (pinfunction "GND_H8") (pintype "power_in"))
      (node (ref "U4") (pin "J18") (pinfunction "GND_J18") (pintype "power_in"))
      (node (ref "U4") (pin "J4") (pinfunction "GNDANAOUT_J4") (pintype "power_in"))
      (node (ref "U4") (pin "K11") (pinfunction "GND_K11") (pintype "power_in"))
      (node (ref "U4") (pin "L1") (pinfunction "GND_L1") (pintype "power_in"))
      (node (ref "U4") (pin "L15") (pinfunction "GND_L15") (pintype "power_in"))
      (node (ref "U4") (pin "L21") (pinfunction "GND_L21") (pintype "power_in"))
      (node (ref "U4") (pin "N18") (pinfunction "GND_N18") (pintype "power_in"))
      (node (ref "U4") (pin "P14") (pinfunction "GND_P14") (pintype "power_in"))
      (node (ref "U4") (pin "P21") (pinfunction "GND_P21") (pintype "power_in"))
      (node (ref "U4") (pin "R11") (pinfunction "GNDBAT_R11") (pintype "power_in"))
      (node (ref "U4") (pin "R15") (pinfunction "GNDDPHY_R15") (pintype "power_in"))
      (node (ref "U4") (pin "R17") (pinfunction "GND_R17") (pintype "power_in"))
      (node (ref "U4") (pin "T17") (pinfunction "GND_T17") (pintype "power_in"))
      (node (ref "U4") (pin "U15") (pinfunction "GNDDPHY_U15") (pintype "power_in"))
      (node (ref "U4") (pin "U21") (pinfunction "GND_U21") (pintype "power_in"))
      (node (ref "U4") (pin "V13") (pinfunction "GND_V13") (pintype "power_in"))
      (node (ref "Y2") (pin "2") (pinfunction "GND_2") (pintype "power_in"))
      (node (ref "Y3") (pin "2") (pinfunction "GND_2") (pintype "power_in"))
      (node (ref "Y3") (pin "4") (pinfunction "GND_4") (pintype "power_in"))
      (node (ref "Y4") (pin "2") (pinfunction "GND_2") (pintype "power_in"))
    )
    (net (code "28") (name "Net-(U4G-HHSA_RTUNE)") (class "Default")
      (node (ref "R23") (pin "1") (pinfunction "1_1") (pintype "passive"))
      (node (ref "U4") (pin "C6") (pinfunction "HHSA_RTUNE_C6") (pintype "input"))
    )
    (net (code "29") (name "Net-(U4G-HHSB_RTUNE)") (class "Default")
      (node (ref "R27") (pin "1") (pinfunction "1_1") (pintype "passive"))
      (node (ref "U4") (pin "D8") (pinfunction "HHSB_RTUNE_D8") (pintype "input"))
    )
    (net (code "30") (name "Net-(U4G-HHSC_RTUNE)") (class "Default")
      (node (ref "R28") (pin "1") (pinfunction "1_1") (pintype "passive"))
      (node (ref "U4") (pin "B7") (pinfunction "HHSC_RTUNE_B7") (pintype "input"))
    )
    (net (code "31") (name "Net-(U4G-JTAGSEL)") (class "Default")
      (node (ref "R26") (pin "2") (pinfunction "2_2") (pintype "passive"))
      (node (ref "U4") (pin "W15") (pinfunction "JTAGSEL_W15") (pintype "input"))
    )
    (net (code "32") (name "Net-(U4G-MIPI_REXT)") (class "Default")
      (node (ref "R33") (pin "1") (pinfunction "1_1") (pintype "passive"))
      (node (ref "U4") (pin "R19") (pinfunction "MIPI_REXT_R19") (pintype "input"))
    )
    (net (code "33") (name "Net-(U4G-QSPI0_CAL)") (class "Default")
      (node (ref "R29") (pin "2") (pinfunction "2_2") (pintype "passive"))
      (node (ref "U4") (pin "P16") (pinfunction "QSPI0_CAL_P16") (pintype "input"))
    )
    (net (code "34") (name "Net-(U4G-SDMMC0_CAL)") (class "Default")
      (node (ref "R30") (pin "2") (pinfunction "2_2") (pintype "passive"))
      (node (ref "U4") (pin "K15") (pinfunction "SDMMC0_CAL_K15") (pintype "input"))
    )
    (net (code "35") (name "Net-(U4G-SDMMC1_CAL)") (class "Default")
      (node (ref "R31") (pin "2") (pinfunction "2_2") (pintype "passive"))
      (node (ref "U4") (pin "J10") (pinfunction "SDMMC1_CAL_J10") (pintype "input"))
    )
    (net (code "36") (name "Net-(U4G-SDMMC2_CAL)") (class "Default")
      (node (ref "R32") (pin "2") (pinfunction "2_2") (pintype "passive"))
      (node (ref "U4") (pin "D14") (pinfunction "SDMMC2_CAL_D14") (pintype "input"))
    )
    (net (code "37") (name "Net-(U4G-TST)") (class "Default")
      (node (ref "R25") (pin "2") (pinfunction "2_2") (pintype "passive"))
      (node (ref "U4") (pin "AA9") (pinfunction "TST_AA9") (pintype "input"))
    )
    (net (code "38") (name "Net-(Y2-OUT)") (class "Default")
      (node (ref "R34") (pin "1") (pinfunction "1_1") (pintype "passive"))
      (node (ref "Y2") (pin "3") (pinfunction "OUT_3") (pintype "output"))
    )
    (net (code "39") (name "Net-(Y4-OUT)") (class "Default")
      (node (ref "R38") (pin "1") (pinfunction "1_1") (pintype "passive"))
      (node (ref "Y4") (pin "3") (pinfunction "OUT_3") (pintype "output"))
    )
    (net (code "40") (name "VDDANA") (class "Default")
      (node (ref "C48") (pin "2") (pinfunction "2_2") (pintype "passive"))
      (node (ref "C70") (pin "1") (pinfunction "1_1") (pintype "passive"))
      (node (ref "C71") (pin "1") (pinfunction "1_1") (pintype "passive"))
      (node (ref "C73") (pin "1") (pinfunction "1_1") (pintype "passive"))
      (node (ref "C79") (pin "1") (pinfunction "1_1") (pintype "passive"))
      (node (ref "C80") (pin "1") (pinfunction "1_1") (pintype "passive"))
      (node (ref "U4") (pin "E5") (pinfunction "VDDANA_E5") (pintype "power_in"))
      (node (ref "U4") (pin "E6") (pinfunction "VDDANA_E6") (pintype "power_in"))
      (node (ref "U4") (pin "G6") (pinfunction "ADVREFP_G6") (pintype "power_in"))
      (node (ref "U4") (pin "J6") (pinfunction "VDDANAOUT_J6") (pintype "power_in"))
      (node (ref "U4") (pin "T15") (pinfunction "VDDDPHY_T15") (pintype "power_in"))
      (node (ref "U4") (pin "T16") (pinfunction "VDDDPHY_T16") (pintype "power_in"))
    )
    (net (code "41") (name "VDDBU") (class "Default")
      (node (ref "C78") (pin "1") (pinfunction "1_1") (pintype "passive"))
      (node (ref "R26") (pin "1") (pinfunction "1_1") (pintype "passive"))
      (node (ref "U4") (pin "P11") (pinfunction "VBAT_P11") (pintype "power_in"))
    )
    (net (code "42") (name "VDDCORE") (class "Default")
      (node (ref "C45") (pin "1") (pinfunction "1_1") (pintype "passive"))
      (node (ref "C46") (pin "1") (pinfunction "1_1") (pintype "passive"))
      (node (ref "C47") (pin "1") (pinfunction "1_1") (pintype "passive"))
      (node (ref "C49") (pin "1") (pinfunction "1_1") (pintype "passive"))
      (node (ref "C50") (pin "1") (pinfunction "1_1") (pintype "passive"))
      (node (ref "C51") (pin "1") (pinfunction "1_1") (pintype "passive"))
      (node (ref "C52") (pin "1") (pinfunction "1_1") (pintype "passive"))
      (node (ref "C53") (pin "1") (pinfunction "1_1") (pintype "passive"))
      (node (ref "C54") (pin "1") (pinfunction "1_1") (pintype "passive"))
      (node (ref "C55") (pin "1") (pinfunction "1_1") (pintype "passive"))
      (node (ref "C56") (pin "1") (pinfunction "1_1") (pintype "passive"))
      (node (ref "C57") (pin "1") (pinfunction "1_1") (pintype "passive"))
      (node (ref "C58") (pin "1") (pinfunction "1_1") (pintype "passive"))
      (node (ref "C59") (pin "1") (pinfunction "1_1") (pintype "passive"))
      (node (ref "C60") (pin "1") (pinfunction "1_1") (pintype "passive"))
      (node (ref "C61") (pin "1") (pinfunction "1_1") (pintype "passive"))
      (node (ref "U4") (pin "F15") (pinfunction "VDDCORE_F15") (pintype "power_in"))
      (node (ref "U4") (pin "F6") (pinfunction "VDDCORE_F6") (pintype "power_in"))
      (node (ref "U4") (pin "F9") (pinfunction "VDDCORE_F9") (pintype "power_in"))
      (node (ref "U4") (pin "J13") (pinfunction "VDDCORE_J13") (pintype "power_in"))
      (node (ref "U4") (pin "J9") (pinfunction "VDDCORE_J9") (pintype "power_in"))
      (node (ref "U4") (pin "L19") (pinfunction "VDDCORE_L19") (pintype "power_in"))
      (node (ref "U4") (pin "L3") (pinfunction "VDDCORE_L3") (pintype "power_in"))
      (node (ref "U4") (pin "N13") (pinfunction "VDDCORE_N13") (pintype "power_in"))
      (node (ref "U4") (pin "P19") (pinfunction "VDDCORE_P19") (pintype "power_in"))
      (node (ref "U4") (pin "U16") (pinfunction "VDDCORE_U16") (pintype "power_in"))
      (node (ref "U4") (pin "U17") (pinfunction "VDDCORE_U17") (pintype "power_in"))
      (node (ref "U4") (pin "U19") (pinfunction "VDDCORE_U19") (pintype "power_in"))
      (node (ref "U4") (pin "W17") (pinfunction "VDDCORE_W17") (pintype "power_in"))
      (node (ref "U4") (pin "Y20") (pinfunction "VDDCORE_Y20") (pintype "power_in"))
    )
    (net (code "43") (name "VDDCPU") (class "Default")
      (node (ref "C30") (pin "1") (pinfunction "1_1") (pintype "passive"))
      (node (ref "C31") (pin "1") (pinfunction "1_1") (pintype "passive"))
      (node (ref "C32") (pin "1") (pinfunction "1_1") (pintype "passive"))
      (node (ref "C33") (pin "1") (pinfunction "1_1") (pintype "passive"))
      (node (ref "C34") (pin "1") (pinfunction "1_1") (pintype "passive"))
      (node (ref "C35") (pin "1") (pinfunction "1_1") (pintype "passive"))
      (node (ref "U4") (pin "B20") (pinfunction "VDDCPU_B20") (pintype "power_in"))
      (node (ref "U4") (pin "E16") (pinfunction "VDDCPU_E16") (pintype "power_in"))
      (node (ref "U4") (pin "E17") (pinfunction "VDDCPU_E17") (pintype "power_in"))
      (node (ref "U4") (pin "E19") (pinfunction "VDDCPU_E19") (pintype "power_in"))
      (node (ref "U4") (pin "F16") (pinfunction "VDDCPU_F16") (pintype "power_in"))
    )
    (net (code "44") (name "VDDIN33") (class "Default")
      (node (ref "C74") (pin "1") (pinfunction "1_1") (pintype "passive"))
      (node (ref "C75") (pin "1") (pinfunction "1_1") (pintype "passive"))
      (node (ref "U4") (pin "H3") (pinfunction "VDDIN33_H3") (pintype "power_in"))
    )
    (net (code "45") (name "VDDSDMMC0") (class "Default")
      (node (ref "C41") (pin "1") (pinfunction "1_1") (pintype "passive"))
      (node (ref "TP14") (pin "1") (pinfunction "1_1") (pintype "passive"))
      (node (ref "U4") (pin "J16") (pinfunction "VDDSDMMC0_J16") (pintype "power_in"))
    )
    (net (code "46") (name "VDDSDMMC1") (class "Default")
      (node (ref "C42") (pin "1") (pinfunction "1_1") (pintype "passive"))
      (node (ref "TP15") (pin "1") (pinfunction "1_1") (pintype "passive"))
      (node (ref "U4") (pin "C11") (pinfunction "VDDSDMMC1_C11") (pintype "power_in"))
    )
    (net (code "47") (name "VDDUTMII") (class "Default")
      (node (ref "C62") (pin "1") (pinfunction "1_1") (pintype "passive"))
      (node (ref "C63") (pin "1") (pinfunction "1_1") (pintype "passive"))
      (node (ref "C65") (pin "1") (pinfunction "1_1") (pintype "passive"))
      (node (ref "C67") (pin "1") (pinfunction "1_1") (pintype "passive"))
      (node (ref "C68") (pin "1") (pinfunction "1_1") (pintype "passive"))
      (node (ref "C69") (pin "1") (pinfunction "1_1") (pintype "passive"))
      (node (ref "U4") (pin "B2") (pinfunction "VDDUTMI_B2") (pintype "power_in"))
      (node (ref "U4") (pin "C5") (pinfunction "VDDUTMI_C5") (pintype "power_in"))
      (node (ref "U4") (pin "C8") (pinfunction "VDDUTMI_C8") (pintype "power_in"))
      (node (ref "U4") (pin "E3") (pinfunction "VDDUTMI_E3") (pintype "power_in"))
      (node (ref "U4") (pin "F7") (pinfunction "VDDUTMI_F7") (pintype "power_in"))
    )
    (net (code "48") (name "VDD_3V3") (class "Default")
      (node (ref "C64") (pin "2") (pinfunction "2_2") (pintype "passive"))
      (node (ref "C77") (pin "2") (pinfunction "2_2") (pintype "passive"))
      (node (ref "R24") (pin "2") (pinfunction "2_2") (pintype "passive"))
      (node (ref "Y2") (pin "4") (pinfunction "VDD_4") (pintype "power_in"))
      (node (ref "Y4") (pin "1") (pinfunction "~{STB}_1") (pintype "input"))
      (node (ref "Y4") (pin "4") (pinfunction "VDD_4") (pintype "power_in"))
    )
    (net (code "49") (name "VDD_3V3_MPU") (class "Default")
      (node (ref "C36") (pin "1") (pinfunction "1_1") (pintype "passive"))
      (node (ref "C37") (pin "1") (pinfunction "1_1") (pintype "passive"))
      (node (ref "C38") (pin "1") (pinfunction "1_1") (pintype "passive"))
      (node (ref "C39") (pin "1") (pinfunction "1_1") (pintype "passive"))
      (node (ref "C40") (pin "1") (pinfunction "1_1") (pintype "passive"))
      (node (ref "C43") (pin "1") (pinfunction "1_1") (pintype "passive"))
      (node (ref "C44") (pin "1") (pinfunction "1_1") (pintype "passive"))
      (node (ref "U4") (pin "C14") (pinfunction "VDDIOP1_C14") (pintype "power_in"))
      (node (ref "U4") (pin "C17") (pinfunction "VDDIOP1_C17") (pintype "power_in"))
      (node (ref "U4") (pin "F13") (pinfunction "VDDSDMMC2_F13") (pintype "power_in"))
      (node (ref "U4") (pin "H19") (pinfunction "VDDQSPI1_H19") (pintype "power_in"))
      (node (ref "U4") (pin "N16") (pinfunction "VDDQSPI0_N16") (pintype "power_in"))
      (node (ref "U4") (pin "T13") (pinfunction "VDDIOP0_T13") (pintype "power_in"))
      (node (ref "U4") (pin "W14") (pinfunction "VDDIOP0_W14") (pintype "power_in"))
    )
    (net (code "50") (name "unconnected-(U4G-AUDIOCLK-PadK7)") (class "Default")
      (node (ref "U4") (pin "K7") (pinfunction "AUDIOCLK_K7") (pintype "output+no_connect"))
    )
    (net (code "51") (name "unconnected-(U4G-HHSA_CC1-PadD7)") (class "Default")
      (node (ref "U4") (pin "D7") (pinfunction "HHSA_CC1_D7") (pintype "bidirectional+no_connect"))
    )
    (net (code "52") (name "unconnected-(U4G-HHSA_CC2-PadG9)") (class "Default")
      (node (ref "U4") (pin "G9") (pinfunction "HHSA_CC2_G9") (pintype "bidirectional+no_connect"))
    )
  )
)
